# new.net
KiCad netlist of a schematic drawn in Altium Designer
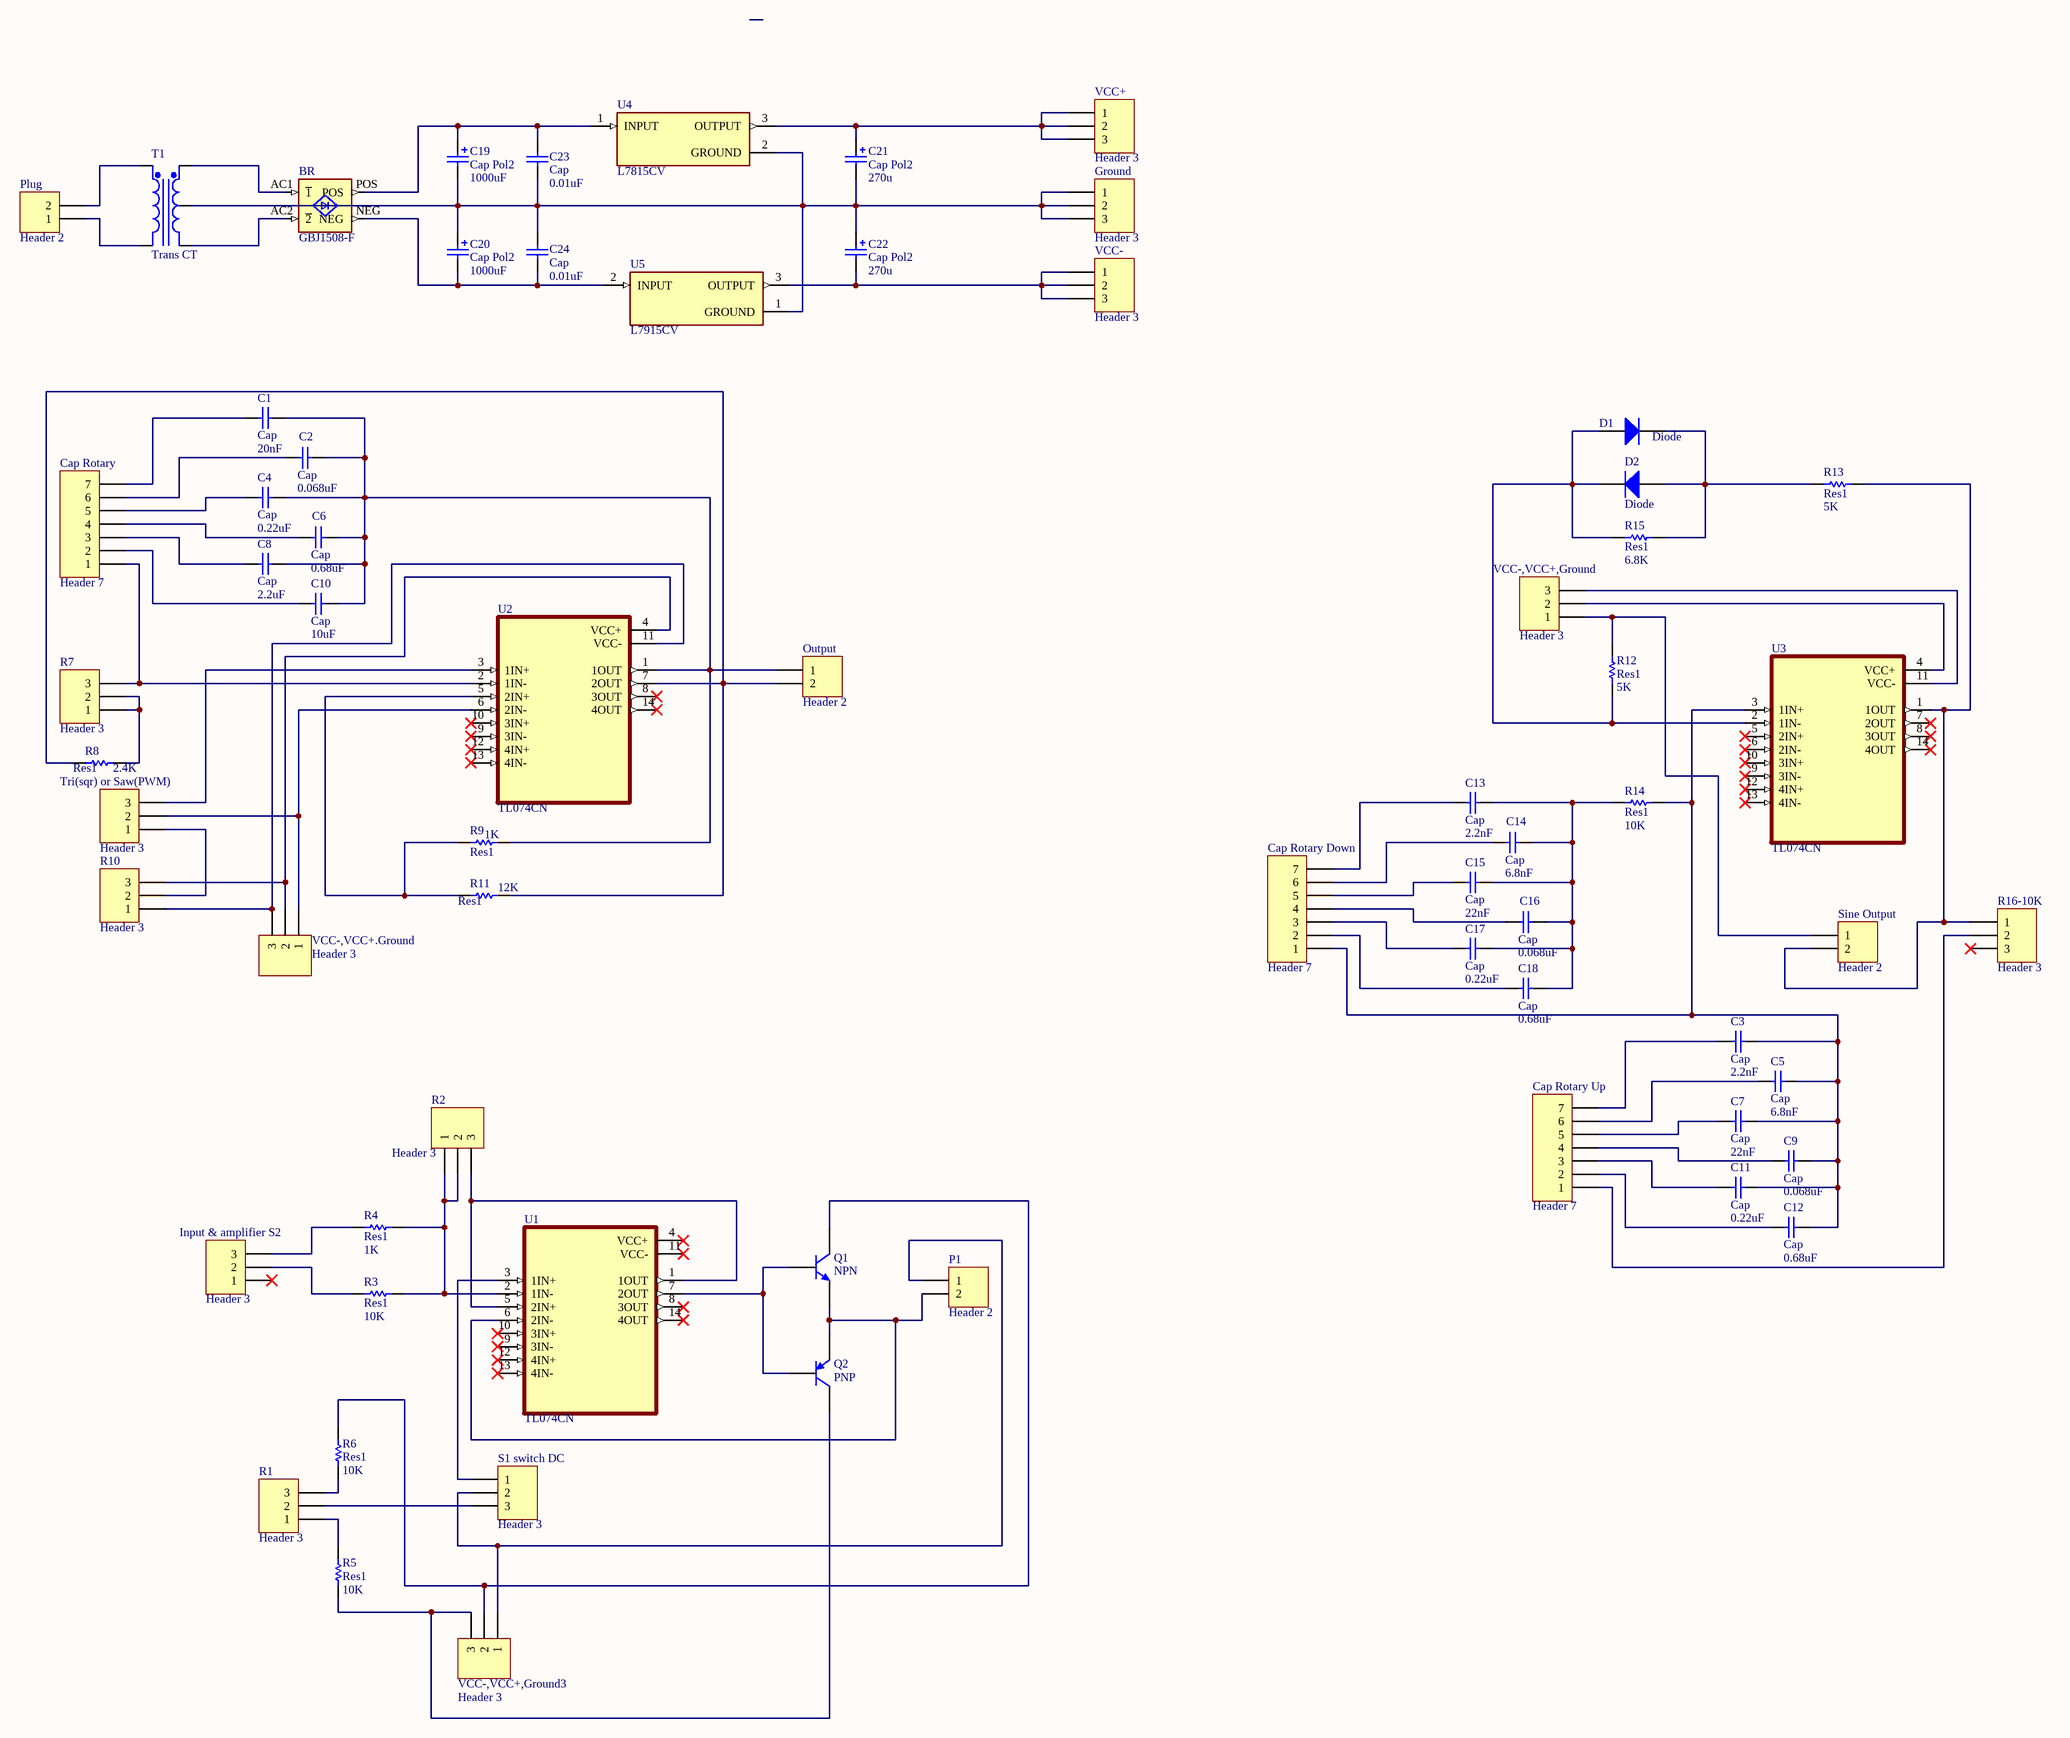
[diagram p0: new.SchDoc]

(export (version "E")
  (design (tool "Eeschema 10.0.6"))
  (components
    (comp (ref "BR")
      (value "GBJ1508-F")
      (footprint "DIO_GBJ1508-F")
      (description "Bridge Rectifier Single Phase Standard 800V Through Hole GBJ")
      (fields (field (name "MF") "Diodes Inc."))
      (libsource (lib "GBJ1508-F") (part "GBJ1508-F"))
    )
    (comp (ref "C1")
      (value "Cap")
      (footprint "RAD-0.3")
      (description "Capacitor")
      (fields (field (name "ALTIUM_VALUE") "20nF") (field (name "PUBLISHER") "Altium Limited"))
      (libsource (lib "Miscellaneous Devices") (part "Cap"))
    )
    (comp (ref "C2")
      (value "Cap")
      (footprint "RAD-0.3")
      (description "Capacitor")
      (fields (field (name "ALTIUM_VALUE") "0.068uF") (field (name "PUBLISHER") "Altium Limited"))
      (libsource (lib "Miscellaneous Devices") (part "Cap"))
    )
    (comp (ref "C3")
      (value "Cap")
      (footprint "RAD-0.3")
      (description "Capacitor")
      (fields (field (name "ALTIUM_VALUE") "2.2nF") (field (name "PUBLISHER") "Altium Limited"))
      (libsource (lib "Miscellaneous Devices") (part "Cap"))
    )
    (comp (ref "C4")
      (value "Cap")
      (footprint "RAD-0.3")
      (description "Capacitor")
      (fields (field (name "ALTIUM_VALUE") "0.22uF") (field (name "PUBLISHER") "Altium Limited"))
      (libsource (lib "Miscellaneous Devices") (part "Cap"))
    )
    (comp (ref "C5")
      (value "Cap")
      (footprint "RAD-0.3")
      (description "Capacitor")
      (fields (field (name "ALTIUM_VALUE") "6.8nF") (field (name "PUBLISHER") "Altium Limited"))
      (libsource (lib "Miscellaneous Devices") (part "Cap"))
    )
    (comp (ref "C6")
      (value "Cap")
      (footprint "RAD-0.3")
      (description "Capacitor")
      (fields (field (name "ALTIUM_VALUE") "0.68uF") (field (name "PUBLISHER") "Altium Limited"))
      (libsource (lib "Miscellaneous Devices") (part "Cap"))
    )
    (comp (ref "C7")
      (value "Cap")
      (footprint "RAD-0.3")
      (description "Capacitor")
      (fields (field (name "ALTIUM_VALUE") "22nF") (field (name "PUBLISHER") "Altium Limited"))
      (libsource (lib "Miscellaneous Devices") (part "Cap"))
    )
    (comp (ref "C8")
      (value "Cap")
      (footprint "RAD-0.3")
      (description "Capacitor")
      (fields (field (name "ALTIUM_VALUE") "2.2uF") (field (name "PUBLISHER") "Altium Limited"))
      (libsource (lib "Miscellaneous Devices") (part "Cap"))
    )
    (comp (ref "C9")
      (value "Cap")
      (footprint "RAD-0.3")
      (description "Capacitor")
      (fields (field (name "ALTIUM_VALUE") "0.068uF") (field (name "PUBLISHER") "Altium Limited"))
      (libsource (lib "Miscellaneous Devices") (part "Cap"))
    )
    (comp (ref "C10")
      (value "Cap")
      (footprint "RAD-0.3")
      (description "Capacitor")
      (fields (field (name "ALTIUM_VALUE") "10uF") (field (name "PUBLISHER") "Altium Limited"))
      (libsource (lib "Miscellaneous Devices") (part "Cap"))
    )
    (comp (ref "C11")
      (value "Cap")
      (footprint "RAD-0.3")
      (description "Capacitor")
      (fields (field (name "ALTIUM_VALUE") "0.22uF") (field (name "PUBLISHER") "Altium Limited"))
      (libsource (lib "Miscellaneous Devices") (part "Cap"))
    )
    (comp (ref "C12")
      (value "Cap")
      (footprint "RAD-0.3")
      (description "Capacitor")
      (fields (field (name "ALTIUM_VALUE") "0.68uF") (field (name "PUBLISHER") "Altium Limited"))
      (libsource (lib "Miscellaneous Devices") (part "Cap"))
    )
    (comp (ref "C13")
      (value "Cap")
      (footprint "RAD-0.3")
      (description "Capacitor")
      (fields (field (name "ALTIUM_VALUE") "2.2nF") (field (name "PUBLISHER") "Altium Limited"))
      (libsource (lib "Miscellaneous Devices") (part "Cap"))
    )
    (comp (ref "C14")
      (value "Cap")
      (footprint "RAD-0.3")
      (description "Capacitor")
      (fields (field (name "ALTIUM_VALUE") "6.8nF") (field (name "PUBLISHER") "Altium Limited"))
      (libsource (lib "Miscellaneous Devices") (part "Cap"))
    )
    (comp (ref "C15")
      (value "Cap")
      (footprint "RAD-0.3")
      (description "Capacitor")
      (fields (field (name "ALTIUM_VALUE") "22nF") (field (name "PUBLISHER") "Altium Limited"))
      (libsource (lib "Miscellaneous Devices") (part "Cap"))
    )
    (comp (ref "C16")
      (value "Cap")
      (footprint "RAD-0.3")
      (description "Capacitor")
      (fields (field (name "ALTIUM_VALUE") "0.068uF") (field (name "PUBLISHER") "Altium Limited"))
      (libsource (lib "Miscellaneous Devices") (part "Cap"))
    )
    (comp (ref "C17")
      (value "Cap")
      (footprint "RAD-0.3")
      (description "Capacitor")
      (fields (field (name "ALTIUM_VALUE") "0.22uF") (field (name "PUBLISHER") "Altium Limited"))
      (libsource (lib "Miscellaneous Devices") (part "Cap"))
    )
    (comp (ref "C18")
      (value "Cap")
      (footprint "RAD-0.3")
      (description "Capacitor")
      (fields (field (name "ALTIUM_VALUE") "0.68uF") (field (name "PUBLISHER") "Altium Limited"))
      (libsource (lib "Miscellaneous Devices") (part "Cap"))
    )
    (comp (ref "C19")
      (value "Cap Pol2")
      (footprint "POLAR0.8")
      (description "Polarized Capacitor (Axial)")
      (fields (field (name "ALTIUM_VALUE") "1000uF") (field (name "PUBLISHER") "Altium Limited"))
      (libsource (lib "Miscellaneous Devices") (part "Cap Pol2"))
    )
    (comp (ref "C20")
      (value "Cap Pol2")
      (footprint "POLAR0.8")
      (description "Polarized Capacitor (Axial)")
      (fields (field (name "ALTIUM_VALUE") "1000uF") (field (name "PUBLISHER") "Altium Limited"))
      (libsource (lib "Miscellaneous Devices") (part "Cap Pol2"))
    )
    (comp (ref "C21")
      (value "Cap Pol2")
      (footprint "POLAR0.8")
      (description "Polarized Capacitor (Axial)")
      (fields (field (name "ALTIUM_VALUE") "270u") (field (name "PUBLISHER") "Altium Limited"))
      (libsource (lib "Miscellaneous Devices") (part "Cap Pol2"))
    )
    (comp (ref "C22")
      (value "Cap Pol2")
      (footprint "POLAR0.8")
      (description "Polarized Capacitor (Axial)")
      (fields (field (name "ALTIUM_VALUE") "270u") (field (name "PUBLISHER") "Altium Limited"))
      (libsource (lib "Miscellaneous Devices") (part "Cap Pol2"))
    )
    (comp (ref "C23")
      (value "Cap")
      (footprint "RAD-0.3")
      (description "Capacitor")
      (fields (field (name "ALTIUM_VALUE") "0.01uF") (field (name "PUBLISHER") "Altium Limited"))
      (libsource (lib "Miscellaneous Devices") (part "Cap"))
    )
    (comp (ref "C24")
      (value "Cap")
      (footprint "RAD-0.3")
      (description "Capacitor")
      (fields (field (name "ALTIUM_VALUE") "0.01uF") (field (name "PUBLISHER") "Altium Limited"))
      (libsource (lib "Miscellaneous Devices") (part "Cap"))
    )
    (comp (ref "Cap Rotary")
      (value "Header 7")
      (footprint "HDR1X7")
      (description "Header, 7-Pin")
      (fields (field (name "PUBLISHER") "Altium Limited"))
      (libsource (lib "Miscellaneous Connectors") (part "Header 7"))
    )
    (comp (ref "Cap Rotary Down")
      (value "Header 7")
      (footprint "HDR1X7")
      (description "Header, 7-Pin")
      (fields (field (name "PUBLISHER") "Altium Limited"))
      (libsource (lib "Miscellaneous Connectors") (part "Header 7"))
    )
    (comp (ref "Cap Rotary Up")
      (value "Header 7")
      (footprint "HDR1X7")
      (description "Header, 7-Pin")
      (fields (field (name "PUBLISHER") "Altium Limited"))
      (libsource (lib "Miscellaneous Connectors") (part "Header 7"))
    )
    (comp (ref "D1")
      (value "Diode")
      (footprint "SMC")
      (description "Default Diode")
      (fields (field (name "PUBLISHER") "Altium Limited"))
      (libsource (lib "Miscellaneous Devices") (part "Diode"))
    )
    (comp (ref "D2")
      (value "Diode")
      (footprint "SMC")
      (description "Default Diode")
      (fields (field (name "PUBLISHER") "Altium Limited"))
      (libsource (lib "Miscellaneous Devices") (part "Diode"))
    )
    (comp (ref "Ground")
      (value "Header 3")
      (footprint "HDR1X3")
      (description "Header, 3-Pin")
      (fields (field (name "PUBLISHER") "Altium Limited"))
      (libsource (lib "") (part "Header 3_2"))
    )
    (comp (ref "Input & amplifier S2")
      (value "Header 3")
      (footprint "HDR1X3")
      (description "Header, 3-Pin")
      (fields (field (name "PUBLISHER") "Altium Limited"))
      (libsource (lib "") (part "Header 3_1"))
    )
    (comp (ref "Output")
      (value "Header 2")
      (footprint "HDR1X2")
      (description "Header, 2-Pin")
      (fields (field (name "PUBLISHER") "Altium Limited"))
      (libsource (lib "Miscellaneous Connectors") (part "Header 2"))
    )
    (comp (ref "P1")
      (value "Header 2")
      (footprint "HDR1X2")
      (description "Header, 2-Pin")
      (fields (field (name "PUBLISHER") "Altium Limited"))
      (libsource (lib "Miscellaneous Connectors") (part "Header 2"))
    )
    (comp (ref "Plug")
      (value "Header 2")
      (footprint "HDR1X2")
      (description "Header, 2-Pin")
      (fields (field (name "PUBLISHER") "Altium Limited"))
      (libsource (lib "") (part "Header 2_1"))
    )
    (comp (ref "Q1")
      (value "NPN")
      (footprint "TO-226-AA")
      (description "NPN Bipolar Transistor")
      (fields (field (name "PUBLISHER") "Altium Limited"))
      (libsource (lib "Miscellaneous Devices") (part "NPN"))
    )
    (comp (ref "Q2")
      (value "PNP")
      (footprint "SOT-23B_N")
      (description "PNP Bipolar Transistor")
      (fields (field (name "PUBLISHER") "Altium Limited"))
      (libsource (lib "Miscellaneous Devices") (part "PNP"))
    )
    (comp (ref "R1")
      (value "Header 3")
      (footprint "HDR1X3")
      (description "Header, 3-Pin")
      (fields (field (name "PUBLISHER") "Altium Limited"))
      (libsource (lib "") (part "Header 3_1"))
    )
    (comp (ref "R2")
      (value "Header 3")
      (footprint "HDR1X3")
      (description "Header, 3-Pin")
      (fields (field (name "PUBLISHER") "Altium Limited"))
      (libsource (lib "") (part "Header 3_3"))
    )
    (comp (ref "R3")
      (value "Res1")
      (footprint "AXIAL-0.3")
      (description "Resistor")
      (fields (field (name "ALTIUM_VALUE") "10K") (field (name "PUBLISHER") "Altium Limited"))
      (libsource (lib "Miscellaneous Devices") (part "Res1"))
    )
    (comp (ref "R4")
      (value "Res1")
      (footprint "AXIAL-0.3")
      (description "Resistor")
      (fields (field (name "ALTIUM_VALUE") "1K") (field (name "PUBLISHER") "Altium Limited"))
      (libsource (lib "Miscellaneous Devices") (part "Res1"))
    )
    (comp (ref "R5")
      (value "Res1")
      (footprint "AXIAL-0.3")
      (description "Resistor")
      (fields (field (name "ALTIUM_VALUE") "10K") (field (name "PUBLISHER") "Altium Limited"))
      (libsource (lib "Miscellaneous Devices") (part "Res1"))
    )
    (comp (ref "R6")
      (value "Res1")
      (footprint "AXIAL-0.3")
      (description "Resistor")
      (fields (field (name "ALTIUM_VALUE") "10K") (field (name "PUBLISHER") "Altium Limited"))
      (libsource (lib "Miscellaneous Devices") (part "Res1"))
    )
    (comp (ref "R7")
      (value "Header 3")
      (footprint "HDR1X3")
      (description "Header, 3-Pin")
      (fields (field (name "PUBLISHER") "Altium Limited"))
      (libsource (lib "") (part "Header 3_1"))
    )
    (comp (ref "R8")
      (value "Res1")
      (footprint "AXIAL-0.3")
      (description "Resistor")
      (fields (field (name "ALTIUM_VALUE") "2.4K") (field (name "PUBLISHER") "Altium Limited"))
      (libsource (lib "Miscellaneous Devices") (part "Res1"))
    )
    (comp (ref "R9")
      (value "Res1")
      (footprint "AXIAL-0.3")
      (description "Resistor")
      (fields (field (name "ALTIUM_VALUE") "1K") (field (name "PUBLISHER") "Altium Limited"))
      (libsource (lib "Miscellaneous Devices") (part "Res1"))
    )
    (comp (ref "R10")
      (value "Header 3")
      (footprint "HDR1X3")
      (description "Header, 3-Pin")
      (fields (field (name "PUBLISHER") "Altium Limited"))
      (libsource (lib "") (part "Header 3_1"))
    )
    (comp (ref "R11")
      (value "Res1")
      (footprint "AXIAL-0.3")
      (description "Resistor")
      (fields (field (name "ALTIUM_VALUE") "12K") (field (name "PUBLISHER") "Altium Limited"))
      (libsource (lib "Miscellaneous Devices") (part "Res1"))
    )
    (comp (ref "R12")
      (value "Res1")
      (footprint "AXIAL-0.3")
      (description "Resistor")
      (fields (field (name "ALTIUM_VALUE") "5K") (field (name "PUBLISHER") "Altium Limited"))
      (libsource (lib "Miscellaneous Devices") (part "Res1"))
    )
    (comp (ref "R13")
      (value "Res1")
      (footprint "AXIAL-0.3")
      (description "Resistor")
      (fields (field (name "ALTIUM_VALUE") "5K") (field (name "PUBLISHER") "Altium Limited"))
      (libsource (lib "Miscellaneous Devices") (part "Res1"))
    )
    (comp (ref "R14")
      (value "Res1")
      (footprint "AXIAL-0.3")
      (description "Resistor")
      (fields (field (name "ALTIUM_VALUE") "10K") (field (name "PUBLISHER") "Altium Limited"))
      (libsource (lib "Miscellaneous Devices") (part "Res1"))
    )
    (comp (ref "R15")
      (value "Res1")
      (footprint "AXIAL-0.3")
      (description "Resistor")
      (fields (field (name "ALTIUM_VALUE") "6.8K") (field (name "PUBLISHER") "Altium Limited"))
      (libsource (lib "Miscellaneous Devices") (part "Res1"))
    )
    (comp (ref "R16-10K")
      (value "Header 3")
      (footprint "HDR1X3")
      (description "Header, 3-Pin")
      (fields (field (name "PUBLISHER") "Altium Limited"))
      (libsource (lib "") (part "Header 3_2"))
    )
    (comp (ref "S1 switch DC")
      (value "Header 3")
      (footprint "HDR1X3")
      (description "Header, 3-Pin")
      (fields (field (name "PUBLISHER") "Altium Limited"))
      (libsource (lib "") (part "Header 3_2"))
    )
    (comp (ref "Sine Output")
      (value "Header 2")
      (footprint "HDR1X2")
      (description "Header, 2-Pin")
      (fields (field (name "PUBLISHER") "Altium Limited"))
      (libsource (lib "Miscellaneous Connectors") (part "Header 2"))
    )
    (comp (ref "T1")
      (value "Trans CT")
      (footprint "TRF_5")
      (description "Center-Tapped Transformer (Coupled Inductor Model)")
      (fields (field (name "PUBLISHER") "Altium Limited"))
      (libsource (lib "Miscellaneous Devices") (part "Trans CT"))
    )
    (comp (ref "Tri(sqr) or Saw(PWM)")
      (value "Header 3")
      (footprint "HDR1X3")
      (description "Header, 3-Pin")
      (fields (field (name "PUBLISHER") "Altium Limited"))
      (libsource (lib "") (part "Header 3_1"))
    )
    (comp (ref "U1")
      (value "TL074CN")
      (footprint "DIP794W45P254L1969H508Q14")
      (description "Quad Low-Noise JFET-Input General-Purpose Operational Amplifier 14-PDIP 0 to 70")
      (fields (field (name "MF") "Texas Instruments"))
      (libsource (lib "TL074CN") (part "TL074CN"))
    )
    (comp (ref "U2")
      (value "TL074CN")
      (footprint "DIP794W45P254L1969H508Q14")
      (description "Quad Low-Noise JFET-Input General-Purpose Operational Amplifier 14-PDIP 0 to 70")
      (fields (field (name "MF") "Texas Instruments"))
      (libsource (lib "TL074CN") (part "TL074CN"))
    )
    (comp (ref "U3")
      (value "TL074CN")
      (footprint "DIP794W45P254L1969H508Q14")
      (description "Quad Low-Noise JFET-Input General-Purpose Operational Amplifier 14-PDIP 0 to 70")
      (fields (field (name "MF") "Texas Instruments"))
      (libsource (lib "TL074CN") (part "TL074CN"))
    )
    (comp (ref "U4")
      (value "L7815CV")
      (footprint "TO255P1040X460X1935-3")
      (description "Linear Voltage Regulator IC 1 Output 1.5A TO-220AB")
      (fields (field (name "MF") "STMicroelectronics"))
      (libsource (lib "L7815CV") (part "L7815CV"))
    )
    (comp (ref "U5")
      (value "L7915CV")
      (footprint "TO255P1040X460X1935-3")
      (description "Linear Voltage Regulator IC 1 Output 1.5A TO-220AB")
      (fields (field (name "MF") "STMicroelectronics"))
      (libsource (lib "L7915CV") (part "L7915CV"))
    )
    (comp (ref "VCC+")
      (value "Header 3")
      (footprint "HDR1X3")
      (description "Header, 3-Pin")
      (fields (field (name "PUBLISHER") "Altium Limited"))
      (libsource (lib "") (part "Header 3_2"))
    )
    (comp (ref "VCC-")
      (value "Header 3")
      (footprint "HDR1X3")
      (description "Header, 3-Pin")
      (fields (field (name "PUBLISHER") "Altium Limited"))
      (libsource (lib "") (part "Header 3_2"))
    )
    (comp (ref "VCC-,VCC+,Ground")
      (value "Header 3")
      (footprint "HDR1X3")
      (description "Header, 3-Pin")
      (fields (field (name "PUBLISHER") "Altium Limited"))
      (libsource (lib "") (part "Header 3_1"))
    )
    (comp (ref "VCC-,VCC+,Ground3")
      (value "Header 3")
      (footprint "HDR1X3")
      (description "Header, 3-Pin")
      (fields (field (name "PUBLISHER") "Altium Limited"))
      (libsource (lib "Miscellaneous Connectors") (part "Header 3"))
    )
    (comp (ref "VCC-,VCC+.Ground")
      (value "Header 3")
      (footprint "HDR1X3")
      (description "Header, 3-Pin")
      (fields (field (name "PUBLISHER") "Altium Limited"))
      (libsource (lib "Miscellaneous Connectors") (part "Header 3"))
    )
  )
  (nets
    (net (code "1") (name "Net-(BR-~{1})") (class "Default")
      (node (ref "BR") (pin "AC1") (pinfunction "~{1}_AC1") (pintype "input"))
      (node (ref "T1") (pin "3") (pinfunction "Sec+_3") (pintype "passive"))
    )
    (net (code "2") (name "Net-(BR-~{2})") (class "Default")
      (node (ref "BR") (pin "AC2") (pinfunction "~{2}_AC2") (pintype "input"))
      (node (ref "T1") (pin "5") (pinfunction "Sec-_5") (pintype "passive"))
    )
    (net (code "3") (name "Net-(C1-Pad1)") (class "Default")
      (node (ref "C1") (pin "1") (pinfunction "1_1") (pintype "passive"))
      (node (ref "Cap Rotary") (pin "7") (pinfunction "7_7") (pintype "passive"))
    )
    (net (code "4") (name "Net-(C2-Pad1)") (class "Default")
      (node (ref "C2") (pin "1") (pinfunction "1_1") (pintype "passive"))
      (node (ref "Cap Rotary") (pin "6") (pinfunction "6_6") (pintype "passive"))
    )
    (net (code "5") (name "Net-(C3-Pad1)") (class "Default")
      (node (ref "C3") (pin "1") (pinfunction "1_1") (pintype "passive"))
      (node (ref "Cap Rotary Up") (pin "7") (pinfunction "7_7") (pintype "passive"))
    )
    (net (code "6") (name "Net-(C4-Pad1)") (class "Default")
      (node (ref "C4") (pin "1") (pinfunction "1_1") (pintype "passive"))
      (node (ref "Cap Rotary") (pin "5") (pinfunction "5_5") (pintype "passive"))
    )
    (net (code "7") (name "Net-(C5-Pad1)") (class "Default")
      (node (ref "C5") (pin "1") (pinfunction "1_1") (pintype "passive"))
      (node (ref "Cap Rotary Up") (pin "6") (pinfunction "6_6") (pintype "passive"))
    )
    (net (code "8") (name "Net-(C6-Pad1)") (class "Default")
      (node (ref "C6") (pin "1") (pinfunction "1_1") (pintype "passive"))
      (node (ref "Cap Rotary") (pin "4") (pinfunction "4_4") (pintype "passive"))
    )
    (net (code "9") (name "Net-(C7-Pad1)") (class "Default")
      (node (ref "C7") (pin "1") (pinfunction "1_1") (pintype "passive"))
      (node (ref "Cap Rotary Up") (pin "5") (pinfunction "5_5") (pintype "passive"))
    )
    (net (code "10") (name "Net-(C8-Pad1)") (class "Default")
      (node (ref "C8") (pin "1") (pinfunction "1_1") (pintype "passive"))
      (node (ref "Cap Rotary") (pin "3") (pinfunction "3_3") (pintype "passive"))
    )
    (net (code "11") (name "Net-(C9-Pad1)") (class "Default")
      (node (ref "C9") (pin "1") (pinfunction "1_1") (pintype "passive"))
      (node (ref "Cap Rotary Up") (pin "4") (pinfunction "4_4") (pintype "passive"))
    )
    (net (code "12") (name "Net-(C10-Pad1)") (class "Default")
      (node (ref "C10") (pin "1") (pinfunction "1_1") (pintype "passive"))
      (node (ref "Cap Rotary") (pin "2") (pinfunction "2_2") (pintype "passive"))
    )
    (net (code "13") (name "Net-(C11-Pad1)") (class "Default")
      (node (ref "C11") (pin "1") (pinfunction "1_1") (pintype "passive"))
      (node (ref "Cap Rotary Up") (pin "3") (pinfunction "3_3") (pintype "passive"))
    )
    (net (code "14") (name "Net-(C12-Pad1)") (class "Default")
      (node (ref "C12") (pin "1") (pinfunction "1_1") (pintype "passive"))
      (node (ref "Cap Rotary Up") (pin "2") (pinfunction "2_2") (pintype "passive"))
    )
    (net (code "15") (name "Net-(C13-Pad1)") (class "Default")
      (node (ref "C13") (pin "1") (pinfunction "1_1") (pintype "passive"))
      (node (ref "Cap Rotary Down") (pin "7") (pinfunction "7_7") (pintype "passive"))
    )
    (net (code "16") (name "Net-(C13-Pad2)") (class "Default")
      (node (ref "C13") (pin "2") (pinfunction "2_2") (pintype "passive"))
      (node (ref "C14") (pin "2") (pinfunction "2_2") (pintype "passive"))
      (node (ref "C15") (pin "2") (pinfunction "2_2") (pintype "passive"))
      (node (ref "C16") (pin "2") (pinfunction "2_2") (pintype "passive"))
      (node (ref "C17") (pin "2") (pinfunction "2_2") (pintype "passive"))
      (node (ref "C18") (pin "2") (pinfunction "2_2") (pintype "passive"))
      (node (ref "R14") (pin "1") (pinfunction "1_1") (pintype "passive"))
    )
    (net (code "17") (name "Net-(C14-Pad1)") (class "Default")
      (node (ref "C14") (pin "1") (pinfunction "1_1") (pintype "passive"))
      (node (ref "Cap Rotary Down") (pin "6") (pinfunction "6_6") (pintype "passive"))
    )
    (net (code "18") (name "Net-(C15-Pad1)") (class "Default")
      (node (ref "C15") (pin "1") (pinfunction "1_1") (pintype "passive"))
      (node (ref "Cap Rotary Down") (pin "5") (pinfunction "5_5") (pintype "passive"))
    )
    (net (code "19") (name "Net-(C16-Pad1)") (class "Default")
      (node (ref "C16") (pin "1") (pinfunction "1_1") (pintype "passive"))
      (node (ref "Cap Rotary Down") (pin "4") (pinfunction "4_4") (pintype "passive"))
    )
    (net (code "20") (name "Net-(C17-Pad1)") (class "Default")
      (node (ref "C17") (pin "1") (pinfunction "1_1") (pintype "passive"))
      (node (ref "Cap Rotary Down") (pin "3") (pinfunction "3_3") (pintype "passive"))
    )
    (net (code "21") (name "Net-(C18-Pad1)") (class "Default")
      (node (ref "C18") (pin "1") (pinfunction "1_1") (pintype "passive"))
      (node (ref "Cap Rotary Down") (pin "2") (pinfunction "2_2") (pintype "passive"))
    )
    (net (code "22") (name "Net-(Cap Rotary Up-Pad1)") (class "Default")
      (node (ref "Cap Rotary Up") (pin "1") (pinfunction "1_1") (pintype "passive"))
      (node (ref "R16-10K") (pin "2") (pinfunction "2_2") (pintype "passive"))
    )
    (net (code "23") (name "Net-(D1-A)") (class "Default")
      (node (ref "D1") (pin "1") (pinfunction "A_1") (pintype "passive"))
      (node (ref "D2") (pin "2") (pinfunction "K_2") (pintype "passive"))
      (node (ref "R12") (pin "1") (pinfunction "1_1") (pintype "passive"))
      (node (ref "R15") (pin "1") (pinfunction "1_1") (pintype "passive"))
      (node (ref "U3") (pin "2") (pinfunction "1IN-_2") (pintype "input"))
    )
    (net (code "24") (name "Net-(D1-K)") (class "Default")
      (node (ref "D1") (pin "2") (pinfunction "K_2") (pintype "passive"))
      (node (ref "D2") (pin "1") (pinfunction "A_1") (pintype "passive"))
      (node (ref "R13") (pin "1") (pinfunction "1_1") (pintype "passive"))
      (node (ref "R15") (pin "2") (pinfunction "2_2") (pintype "passive"))
    )
    (net (code "25") (name "Net-(Input & amplifier S2-Pad2)") (class "Default")
      (node (ref "Input & amplifier S2") (pin "2") (pinfunction "2_2") (pintype "passive"))
      (node (ref "R3") (pin "1") (pinfunction "1_1") (pintype "passive"))
    )
    (net (code "26") (name "Net-(Input & amplifier S2-Pad3)") (class "Default")
      (node (ref "Input & amplifier S2") (pin "3") (pinfunction "3_3") (pintype "passive"))
      (node (ref "R4") (pin "1") (pinfunction "1_1") (pintype "passive"))
    )
    (net (code "27") (name "Net-(P1-Pad1)") (class "Default")
      (node (ref "P1") (pin "1") (pinfunction "1_1") (pintype "passive"))
      (node (ref "S1 switch DC") (pin "2") (pinfunction "2_2") (pintype "passive"))
      (node (ref "VCC-,VCC+,Ground3") (pin "1") (pinfunction "1_1") (pintype "passive"))
    )
    (net (code "28") (name "Net-(Q1-B)") (class "Default")
      (node (ref "Q1") (pin "2") (pinfunction "B_2") (pintype "passive"))
      (node (ref "Q2") (pin "2") (pinfunction "B_2") (pintype "passive"))
      (node (ref "U1") (pin "7") (pinfunction "2OUT_7") (pintype "output"))
    )
    (net (code "29") (name "Net-(Q1-C)") (class "Default")
      (node (ref "Q1") (pin "1") (pinfunction "C_1") (pintype "passive"))
      (node (ref "R6") (pin "2") (pinfunction "2_2") (pintype "passive"))
      (node (ref "VCC-,VCC+,Ground3") (pin "2") (pinfunction "2_2") (pintype "passive"))
    )
    (net (code "30") (name "Net-(Q1-E)") (class "Default")
      (node (ref "P1") (pin "2") (pinfunction "2_2") (pintype "passive"))
      (node (ref "Q1") (pin "3") (pinfunction "E_3") (pintype "passive"))
      (node (ref "Q2") (pin "3") (pinfunction "E_3") (pintype "passive"))
      (node (ref "U1") (pin "6") (pinfunction "2IN-_6") (pintype "input"))
    )
    (net (code "31") (name "Net-(Q2-C)") (class "Default")
      (node (ref "Q2") (pin "1") (pinfunction "C_1") (pintype "passive"))
      (node (ref "R5") (pin "1") (pinfunction "1_1") (pintype "passive"))
      (node (ref "VCC-,VCC+,Ground3") (pin "3") (pinfunction "3_3") (pintype "passive"))
    )
    (net (code "32") (name "Net-(R1-Pad1)") (class "Default")
      (node (ref "R1") (pin "1") (pinfunction "1_1") (pintype "passive"))
      (node (ref "R5") (pin "2") (pinfunction "2_2") (pintype "passive"))
    )
    (net (code "33") (name "Net-(R1-Pad2)") (class "Default")
      (node (ref "R1") (pin "2") (pinfunction "2_2") (pintype "passive"))
      (node (ref "S1 switch DC") (pin "3") (pinfunction "3_3") (pintype "passive"))
    )
    (net (code "34") (name "Net-(R1-Pad3)") (class "Default")
      (node (ref "R1") (pin "3") (pinfunction "3_3") (pintype "passive"))
      (node (ref "R6") (pin "1") (pinfunction "1_1") (pintype "passive"))
    )
    (net (code "35") (name "Net-(R7-Pad1)") (class "Default")
      (node (ref "R7") (pin "1") (pinfunction "1_1") (pintype "passive"))
      (node (ref "R7") (pin "2") (pinfunction "2_2") (pintype "passive"))
      (node (ref "R8") (pin "2") (pinfunction "2_2") (pintype "passive"))
    )
    (net (code "36") (name "Net-(R10-Pad2)") (class "Default")
      (node (ref "R10") (pin "2") (pinfunction "2_2") (pintype "passive"))
      (node (ref "Tri(sqr) or Saw(PWM)") (pin "1") (pinfunction "1_1") (pintype "passive"))
    )
    (net (code "37") (name "Net-(R12-Pad2)") (class "Default")
      (node (ref "R12") (pin "2") (pinfunction "2_2") (pintype "passive"))
      (node (ref "Sine Output") (pin "1") (pinfunction "1_1") (pintype "passive"))
      (node (ref "VCC-,VCC+,Ground") (pin "1") (pinfunction "1_1") (pintype "passive"))
    )
    (net (code "38") (name "Net-(T1-Pri+)") (class "Default")
      (node (ref "Plug") (pin "2") (pinfunction "2_2") (pintype "passive"))
      (node (ref "T1") (pin "1") (pinfunction "Pri+_1") (pintype "passive"))
    )
    (net (code "39") (name "Net-(T1-Pri-)") (class "Default")
      (node (ref "Plug") (pin "1") (pinfunction "1_1") (pintype "passive"))
      (node (ref "T1") (pin "2") (pinfunction "Pri-_2") (pintype "passive"))
    )
    (net (code "40") (name "Net-(T1-SecCT)") (class "Default")
      (node (ref "C19") (pin "2") (pinfunction "2_2") (pintype "passive"))
      (node (ref "C20") (pin "1") (pinfunction "1_1") (pintype "passive"))
      (node (ref "C21") (pin "2") (pinfunction "2_2") (pintype "passive"))
      (node (ref "C22") (pin "1") (pinfunction "1_1") (pintype "passive"))
      (node (ref "C23") (pin "1") (pinfunction "1_1") (pintype "passive"))
      (node (ref "C24") (pin "2") (pinfunction "2_2") (pintype "passive"))
      (node (ref "Ground") (pin "1") (pinfunction "1_1") (pintype "passive"))
      (node (ref "Ground") (pin "2") (pinfunction "2_2") (pintype "passive"))
      (node (ref "Ground") (pin "3") (pinfunction "3_3") (pintype "passive"))
      (node (ref "T1") (pin "4") (pinfunction "SecCT_4") (pintype "passive"))
      (node (ref "U4") (pin "2") (pinfunction "GROUND_2") (pintype "power_in"))
      (node (ref "U5") (pin "1") (pinfunction "GROUND_1") (pintype "power_in"))
    )
    (net (code "41") (name "Net-(U1-1IN+)") (class "Default")
      (node (ref "S1 switch DC") (pin "1") (pinfunction "1_1") (pintype "passive"))
      (node (ref "U1") (pin "3") (pinfunction "1IN+_3") (pintype "input"))
    )
    (net (code "42") (name "Net-(U1-1IN-)") (class "Default")
      (node (ref "R2") (pin "1") (pinfunction "1_1") (pintype "passive"))
      (node (ref "R2") (pin "2") (pinfunction "2_2") (pintype "passive"))
      (node (ref "R3") (pin "2") (pinfunction "2_2") (pintype "passive"))
      (node (ref "R4") (pin "2") (pinfunction "2_2") (pintype "passive"))
      (node (ref "U1") (pin "2") (pinfunction "1IN-_2") (pintype "input"))
    )
    (net (code "43") (name "Net-(U1-1OUT)") (class "Default")
      (node (ref "R2") (pin "3") (pinfunction "3_3") (pintype "passive"))
      (node (ref "U1") (pin "1") (pinfunction "1OUT_1") (pintype "output"))
      (node (ref "U1") (pin "5") (pinfunction "2IN+_5") (pintype "input"))
    )
    (net (code "44") (name "Net-(U2-1IN+)") (class "Default")
      (node (ref "Tri(sqr) or Saw(PWM)") (pin "3") (pinfunction "3_3") (pintype "passive"))
      (node (ref "U2") (pin "3") (pinfunction "1IN+_3") (pintype "input"))
    )
    (net (code "45") (name "Net-(U2-1IN-)") (class "Default")
      (node (ref "Cap Rotary") (pin "1") (pinfunction "1_1") (pintype "passive"))
      (node (ref "R7") (pin "3") (pinfunction "3_3") (pintype "passive"))
      (node (ref "U2") (pin "2") (pinfunction "1IN-_2") (pintype "input"))
    )
    (net (code "46") (name "Net-(U2-1OUT)") (class "Default")
      (node (ref "C1") (pin "2") (pinfunction "2_2") (pintype "passive"))
      (node (ref "C10") (pin "2") (pinfunction "2_2") (pintype "passive"))
      (node (ref "C2") (pin "2") (pinfunction "2_2") (pintype "passive"))
      (node (ref "C4") (pin "2") (pinfunction "2_2") (pintype "passive"))
      (node (ref "C6") (pin "2") (pinfunction "2_2") (pintype "passive"))
      (node (ref "C8") (pin "2") (pinfunction "2_2") (pintype "passive"))
      (node (ref "Output") (pin "1") (pinfunction "1_1") (pintype "passive"))
      (node (ref "R9") (pin "1") (pinfunction "1_1") (pintype "passive"))
      (node (ref "U2") (pin "1") (pinfunction "1OUT_1") (pintype "output"))
    )
    (net (code "47") (name "Net-(U2-2IN+)") (class "Default")
      (node (ref "R11") (pin "1") (pinfunction "1_1") (pintype "passive"))
      (node (ref "R9") (pin "2") (pinfunction "2_2") (pintype "passive"))
      (node (ref "U2") (pin "5") (pinfunction "2IN+_5") (pintype "input"))
    )
    (net (code "48") (name "Net-(U2-2IN-)") (class "Default")
      (node (ref "Tri(sqr) or Saw(PWM)") (pin "2") (pinfunction "2_2") (pintype "passive"))
      (node (ref "U2") (pin "6") (pinfunction "2IN-_6") (pintype "input"))
      (node (ref "VCC-,VCC+.Ground") (pin "1") (pinfunction "1_1") (pintype "passive"))
    )
    (net (code "49") (name "Net-(U2-2OUT)") (class "Default")
      (node (ref "Output") (pin "2") (pinfunction "2_2") (pintype "passive"))
      (node (ref "R11") (pin "2") (pinfunction "2_2") (pintype "passive"))
      (node (ref "R8") (pin "1") (pinfunction "1_1") (pintype "passive"))
      (node (ref "U2") (pin "7") (pinfunction "2OUT_7") (pintype "output"))
    )
    (net (code "50") (name "Net-(U2-VCC+)") (class "Default")
      (node (ref "R10") (pin "3") (pinfunction "3_3") (pintype "passive"))
      (node (ref "U2") (pin "4") (pinfunction "VCC+_4") (pintype "power_in"))
      (node (ref "VCC-,VCC+.Ground") (pin "2") (pinfunction "2_2") (pintype "passive"))
    )
    (net (code "51") (name "Net-(U2-VCC-)") (class "Default")
      (node (ref "R10") (pin "1") (pinfunction "1_1") (pintype "passive"))
      (node (ref "U2") (pin "11") (pinfunction "VCC-_11") (pintype "power_in"))
      (node (ref "VCC-,VCC+.Ground") (pin "3") (pinfunction "3_3") (pintype "passive"))
    )
    (net (code "52") (name "Net-(U3-1IN+)") (class "Default")
      (node (ref "C11") (pin "2") (pinfunction "2_2") (pintype "passive"))
      (node (ref "C12") (pin "2") (pinfunction "2_2") (pintype "passive"))
      (node (ref "C3") (pin "2") (pinfunction "2_2") (pintype "passive"))
      (node (ref "C5") (pin "2") (pinfunction "2_2") (pintype "passive"))
      (node (ref "C7") (pin "2") (pinfunction "2_2") (pintype "passive"))
      (node (ref "C9") (pin "2") (pinfunction "2_2") (pintype "passive"))
      (node (ref "Cap Rotary Down") (pin "1") (pinfunction "1_1") (pintype "passive"))
      (node (ref "R14") (pin "2") (pinfunction "2_2") (pintype "passive"))
      (node (ref "U3") (pin "3") (pinfunction "1IN+_3") (pintype "input"))
    )
    (net (code "53") (name "Net-(U3-1OUT)") (class "Default")
      (node (ref "R13") (pin "2") (pinfunction "2_2") (pintype "passive"))
      (node (ref "R16-10K") (pin "1") (pinfunction "1_1") (pintype "passive"))
      (node (ref "Sine Output") (pin "2") (pinfunction "2_2") (pintype "passive"))
      (node (ref "U3") (pin "1") (pinfunction "1OUT_1") (pintype "output"))
    )
    (net (code "54") (name "Net-(U3-VCC+)") (class "Default")
      (node (ref "U3") (pin "4") (pinfunction "VCC+_4") (pintype "power_in"))
      (node (ref "VCC-,VCC+,Ground") (pin "2") (pinfunction "2_2") (pintype "passive"))
    )
    (net (code "55") (name "Net-(U3-VCC-)") (class "Default")
      (node (ref "U3") (pin "11") (pinfunction "VCC-_11") (pintype "power_in"))
      (node (ref "VCC-,VCC+,Ground") (pin "3") (pinfunction "3_3") (pintype "passive"))
    )
    (net (code "56") (name "Net-(U4-INPUT)") (class "Default")
      (node (ref "BR") (pin "POS") (pinfunction "POS_POS") (pintype "output"))
      (node (ref "C19") (pin "1") (pinfunction "1_1") (pintype "passive"))
      (node (ref "C23") (pin "2") (pinfunction "2_2") (pintype "passive"))
      (node (ref "U4") (pin "1") (pinfunction "INPUT_1") (pintype "input"))
    )
    (net (code "57") (name "Net-(U4-OUTPUT)") (class "Default")
      (node (ref "C21") (pin "1") (pinfunction "1_1") (pintype "passive"))
      (node (ref "U4") (pin "3") (pinfunction "OUTPUT_3") (pintype "output"))
      (node (ref "VCC+") (pin "1") (pinfunction "1_1") (pintype "passive"))
      (node (ref "VCC+") (pin "2") (pinfunction "2_2") (pintype "passive"))
      (node (ref "VCC+") (pin "3") (pinfunction "3_3") (pintype "passive"))
    )
    (net (code "58") (name "Net-(U5-INPUT)") (class "Default")
      (node (ref "BR") (pin "NEG") (pinfunction "NEG_NEG") (pintype "output"))
      (node (ref "C20") (pin "2") (pinfunction "2_2") (pintype "passive"))
      (node (ref "C24") (pin "1") (pinfunction "1_1") (pintype "passive"))
      (node (ref "U5") (pin "2") (pinfunction "INPUT_2") (pintype "input"))
    )
    (net (code "59") (name "Net-(U5-OUTPUT)") (class "Default")
      (node (ref "C22") (pin "2") (pinfunction "2_2") (pintype "passive"))
      (node (ref "U5") (pin "3") (pinfunction "OUTPUT_3") (pintype "output"))
      (node (ref "VCC-") (pin "1") (pinfunction "1_1") (pintype "passive"))
      (node (ref "VCC-") (pin "2") (pinfunction "2_2") (pintype "passive"))
      (node (ref "VCC-") (pin "3") (pinfunction "3_3") (pintype "passive"))
    )
    (net (code "60") (name "unconnected-(Input & amplifier S2-Pad1)") (class "Default")
      (node (ref "Input & amplifier S2") (pin "1") (pinfunction "1_1") (pintype "passive+no_connect"))
    )
    (net (code "61") (name "unconnected-(R16-10K-Pad3)") (class "Default")
      (node (ref "R16-10K") (pin "3") (pinfunction "3_3") (pintype "passive+no_connect"))
    )
    (net (code "62") (name "unconnected-(U1-3IN+-Pad10)") (class "Default")
      (node (ref "U1") (pin "10") (pinfunction "3IN+_10") (pintype "input+no_connect"))
    )
    (net (code "63") (name "unconnected-(U1-3IN--Pad9)") (class "Default")
      (node (ref "U1") (pin "9") (pinfunction "3IN-_9") (pintype "input+no_connect"))
    )
    (net (code "64") (name "unconnected-(U1-3OUT-Pad8)") (class "Default")
      (node (ref "U1") (pin "8") (pinfunction "3OUT_8") (pintype "output+no_connect"))
    )
    (net (code "65") (name "unconnected-(U1-4IN+-Pad12)") (class "Default")
      (node (ref "U1") (pin "12") (pinfunction "4IN+_12") (pintype "input+no_connect"))
    )
    (net (code "66") (name "unconnected-(U1-4IN--Pad13)") (class "Default")
      (node (ref "U1") (pin "13") (pinfunction "4IN-_13") (pintype "input+no_connect"))
    )
    (net (code "67") (name "unconnected-(U1-4OUT-Pad14)") (class "Default")
      (node (ref "U1") (pin "14") (pinfunction "4OUT_14") (pintype "output+no_connect"))
    )
    (net (code "68") (name "unconnected-(U1-VCC+-Pad4)") (class "Default")
      (node (ref "U1") (pin "4") (pinfunction "VCC+_4") (pintype "power_in+no_connect"))
    )
    (net (code "69") (name "unconnected-(U1-VCC--Pad11)") (class "Default")
      (node (ref "U1") (pin "11") (pinfunction "VCC-_11") (pintype "power_in+no_connect"))
    )
    (net (code "70") (name "unconnected-(U2-3IN+-Pad10)") (class "Default")
      (node (ref "U2") (pin "10") (pinfunction "3IN+_10") (pintype "input+no_connect"))
    )
    (net (code "71") (name "unconnected-(U2-3IN--Pad9)") (class "Default")
      (node (ref "U2") (pin "9") (pinfunction "3IN-_9") (pintype "input+no_connect"))
    )
    (net (code "72") (name "unconnected-(U2-3OUT-Pad8)") (class "Default")
      (node (ref "U2") (pin "8") (pinfunction "3OUT_8") (pintype "output+no_connect"))
    )
    (net (code "73") (name "unconnected-(U2-4IN+-Pad12)") (class "Default")
      (node (ref "U2") (pin "12") (pinfunction "4IN+_12") (pintype "input+no_connect"))
    )
    (net (code "74") (name "unconnected-(U2-4IN--Pad13)") (class "Default")
      (node (ref "U2") (pin "13") (pinfunction "4IN-_13") (pintype "input+no_connect"))
    )
    (net (code "75") (name "unconnected-(U2-4OUT-Pad14)") (class "Default")
      (node (ref "U2") (pin "14") (pinfunction "4OUT_14") (pintype "output+no_connect"))
    )
    (net (code "76") (name "unconnected-(U3-2IN+-Pad5)") (class "Default")
      (node (ref "U3") (pin "5") (pinfunction "2IN+_5") (pintype "input+no_connect"))
    )
    (net (code "77") (name "unconnected-(U3-2IN--Pad6)") (class "Default")
      (node (ref "U3") (pin "6") (pinfunction "2IN-_6") (pintype "input+no_connect"))
    )
    (net (code "78") (name "unconnected-(U3-2OUT-Pad7)") (class "Default")
      (node (ref "U3") (pin "7") (pinfunction "2OUT_7") (pintype "output+no_connect"))
    )
    (net (code "79") (name "unconnected-(U3-3IN+-Pad10)") (class "Default")
      (node (ref "U3") (pin "10") (pinfunction "3IN+_10") (pintype "input+no_connect"))
    )
    (net (code "80") (name "unconnected-(U3-3IN--Pad9)") (class "Default")
      (node (ref "U3") (pin "9") (pinfunction "3IN-_9") (pintype "input+no_connect"))
    )
    (net (code "81") (name "unconnected-(U3-3OUT-Pad8)") (class "Default")
      (node (ref "U3") (pin "8") (pinfunction "3OUT_8") (pintype "output+no_connect"))
    )
    (net (code "82") (name "unconnected-(U3-4IN+-Pad12)") (class "Default")
      (node (ref "U3") (pin "12") (pinfunction "4IN+_12") (pintype "input+no_connect"))
    )
    (net (code "83") (name "unconnected-(U3-4IN--Pad13)") (class "Default")
      (node (ref "U3") (pin "13") (pinfunction "4IN-_13") (pintype "input+no_connect"))
    )
    (net (code "84") (name "unconnected-(U3-4OUT-Pad14)") (class "Default")
      (node (ref "U3") (pin "14") (pinfunction "4OUT_14") (pintype "output+no_connect"))
    )
  )
)
